# TheStaticTurtle_oshw-sdi3g-fiber__schema.net
KiCad netlist of a schematic drawn in Altium Designer
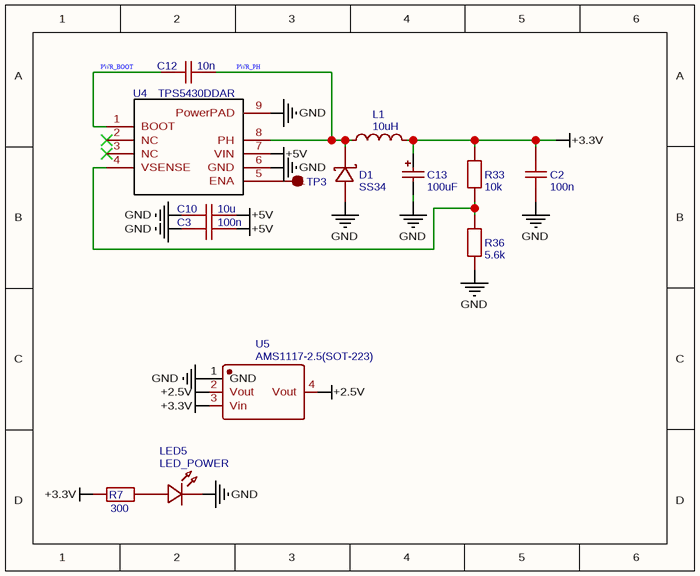
[diagram p0: TheStaticTurtle_oshw-sdi3g-fiber__schematic_V4-Reclocked_OSHW_BiDi_SDI_Fiber_Converter_V4_Reclocker_2024-11-17__Power.schdoc]

(export (version "E")
  (design (tool "Eeschema 10.0.6"))
  (components
    (comp (ref "C2")
      (value "100n")
      (fields (field (name "CONTRIBUTOR") "LCEDA_Lib"))
      (libsource (lib "altium-import") (part "root_1_100n_"))
    )
    (comp (ref "C3")
      (value "100n")
      (fields (field (name "CONTRIBUTOR") "LCEDA_Lib"))
      (libsource (lib "altium-import") (part "root_0_100n_"))
    )
    (comp (ref "C10")
      (value "10u")
      (fields (field (name "CONTRIBUTOR") "LCEDA_Lib"))
      (libsource (lib "altium-import") (part "root_0_10u_"))
    )
    (comp (ref "C12")
      (value "10n")
      (fields (field (name "CONTRIBUTOR") "LCEDA_Lib"))
      (libsource (lib "altium-import") (part "root_0_10n_"))
    )
    (comp (ref "C13")
      (value "100uF")
      (fields (field (name "MANUFACTURER") "Kyocera AVX") (field (name "MANUFACTURER PART") "TAJB107K006RNJ"))
      (libsource (lib "altium-import") (part "root_1_100uF_"))
    )
    (comp (ref "D1")
      (value "SS34")
      (fields (field (name "MANUFACTURER") "MDD(辰达半导体)"))
      (libsource (lib "altium-import") (part "root_3_SS34_"))
    )
    (comp (ref "L1")
      (value "10uH")
      (fields (field (name "MANUFACTURER") "Sunlord(顺络)") (field (name "MANUFACTURER PART") "SWPA4030S100MT"))
      (libsource (lib "altium-import") (part "root_0_10uH_"))
    )
    (comp (ref "LED5")
      (value "LED_POWER")
      (fields
        (field (name "MANUFACTURER") "方舟 ARKLED")
        (field (name "MANUFACTURER PART") "D-B080508B1-KS2")
        (field (name "CONTRIBUTOR") "LCEDA_Lib")
      )
      (libsource (lib "altium-import") (part "root_0_LED_POWER_"))
    )
    (comp (ref "R7")
      (value "300")
      (fields (field (name "CONTRIBUTOR") "LCEDA_Lib"))
      (libsource (lib "altium-import") (part "root_2_300_"))
    )
    (comp (ref "R33")
      (value "10k")
      (fields (field (name "CONTRIBUTOR") "LCEDA_Lib"))
      (libsource (lib "altium-import") (part "root_3_10k_"))
    )
    (comp (ref "R36")
      (value "5.6k")
      (fields (field (name "CONTRIBUTOR") "LCEDA_Lib"))
      (libsource (lib "altium-import") (part "root_3_5.6k_"))
    )
    (comp (ref "TP3")
      (value "TEST-POINT-PTH-1X1")
      (libsource (lib "altium-import") (part "root_2_TEST-POINT-PTH-1X1_"))
    )
    (comp (ref "U4")
      (value "TPS5430DDAR")
      (fields (field (name "MANUFACTURER") "TI(德州仪器)"))
      (libsource (lib "altium-import") (part "root_0_TPS5430DDAR_"))
    )
    (comp (ref "U5")
      (value "AMS1117-2.5(SOT-223)")
      (fields (field (name "MANUFACTURER") "HXY MOSFET(华轩阳电子)") (field (name "CONTRIBUTOR") "lcsc"))
      (libsource (lib "altium-import") (part "root_0_AMS1117-2.5(SOT-223)_"))
    )
  )
  (nets
    (net (code "1") (name "+2.5V") (class "Default")
      (node (ref "U5") (pin "2") (pinfunction "Vout_2") (pintype "passive"))
      (node (ref "U5") (pin "4") (pinfunction "Vout_4") (pintype "passive"))
    )
    (net (code "2") (name "+3.3V") (class "Default")
      (node (ref "C13") (pin "1") (pinfunction "1_1") (pintype "passive"))
      (node (ref "C2") (pin "2") (pinfunction "2_2") (pintype "passive"))
      (node (ref "L1") (pin "2") (pinfunction "2_2") (pintype "passive"))
      (node (ref "R33") (pin "1") (pinfunction "1_1") (pintype "passive"))
      (node (ref "R7") (pin "2") (pinfunction "2_2") (pintype "passive"))
      (node (ref "U5") (pin "3") (pinfunction "Vin_3") (pintype "passive"))
    )
    (net (code "3") (name "+5V") (class "Default")
      (node (ref "C10") (pin "2") (pinfunction "2_2") (pintype "passive"))
      (node (ref "C3") (pin "2") (pinfunction "2_2") (pintype "passive"))
      (node (ref "U4") (pin "7") (pinfunction "VIN_7") (pintype "passive"))
    )
    (net (code "4") (name "/PWR_BOOT") (class "Default")
      (node (ref "C12") (pin "1") (pinfunction "1_1") (pintype "passive"))
      (node (ref "U4") (pin "1") (pinfunction "BOOT_1") (pintype "passive"))
    )
    (net (code "5") (name "/PWR_PH") (class "Default")
      (node (ref "C12") (pin "2") (pinfunction "2_2") (pintype "passive"))
      (node (ref "D1") (pin "1") (pinfunction "K_1") (pintype "passive"))
      (node (ref "L1") (pin "1") (pinfunction "1_1") (pintype "passive"))
      (node (ref "U4") (pin "8") (pinfunction "PH_8") (pintype "passive"))
    )
    (net (code "6") (name "GND") (class "Default")
      (node (ref "C10") (pin "1") (pinfunction "1_1") (pintype "passive"))
      (node (ref "C13") (pin "2") (pinfunction "2_2") (pintype "passive"))
      (node (ref "C2") (pin "1") (pinfunction "1_1") (pintype "passive"))
      (node (ref "C3") (pin "1") (pinfunction "1_1") (pintype "passive"))
      (node (ref "D1") (pin "2") (pinfunction "A_2") (pintype "passive"))
      (node (ref "LED5") (pin "2") (pinfunction "2_2") (pintype "passive"))
      (node (ref "R36") (pin "2") (pinfunction "2_2") (pintype "passive"))
      (node (ref "U4") (pin "6") (pinfunction "GND_6") (pintype "passive"))
      (node (ref "U4") (pin "9") (pinfunction "PowerPAD_9") (pintype "passive"))
      (node (ref "U5") (pin "1") (pinfunction "GND_1") (pintype "passive"))
    )
    (net (code "7") (name "Net-(LED5-Pad1)") (class "Default")
      (node (ref "LED5") (pin "1") (pinfunction "1_1") (pintype "passive"))
      (node (ref "R7") (pin "1") (pinfunction "1_1") (pintype "passive"))
    )
    (net (code "8") (name "Net-(U4-ENA)") (class "Default")
      (node (ref "TP3") (pin "1") (pinfunction "1_1") (pintype "passive"))
      (node (ref "U4") (pin "5") (pinfunction "ENA_5") (pintype "passive"))
    )
    (net (code "9") (name "Net-(U4-VSENSE)") (class "Default")
      (node (ref "R33") (pin "2") (pinfunction "2_2") (pintype "passive"))
      (node (ref "R36") (pin "1") (pinfunction "1_1") (pintype "passive"))
      (node (ref "U4") (pin "4") (pinfunction "VSENSE_4") (pintype "passive"))
    )
    (net (code "10") (name "unconnected-(U4-NC-Pad2)") (class "Default")
      (node (ref "U4") (pin "2") (pinfunction "NC_2") (pintype "passive+no_connect"))
    )
    (net (code "11") (name "unconnected-(U4-NC-Pad3)") (class "Default")
      (node (ref "U4") (pin "3") (pinfunction "NC_3") (pintype "passive+no_connect"))
    )
  )
)
